# Proiect_TSC_v50.net
KiCad netlist of a schematic drawn in EAGLE
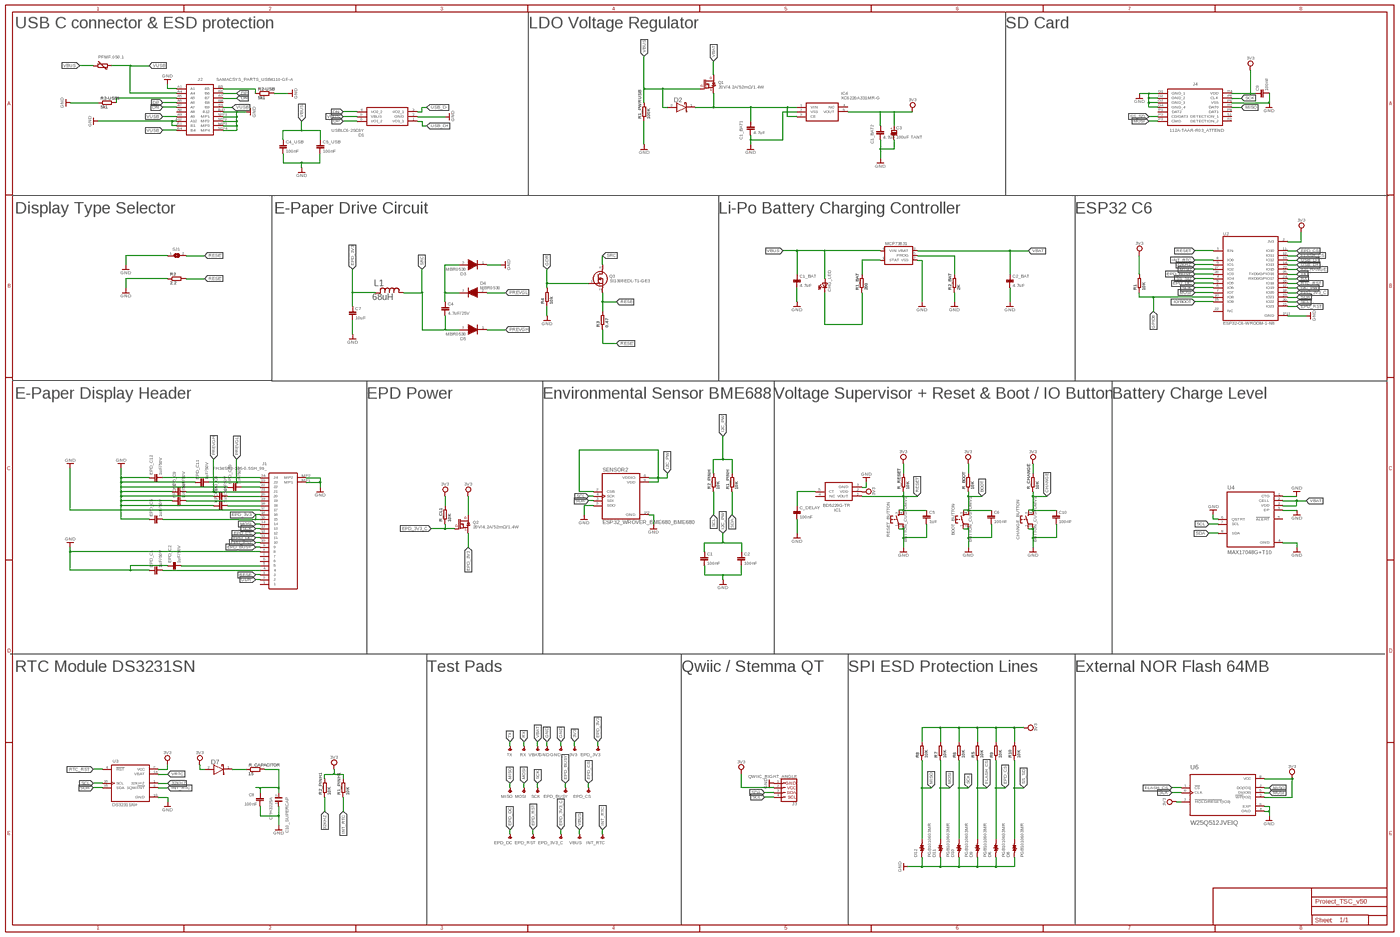
[diagram p0: schematic, sheet 1, overview]
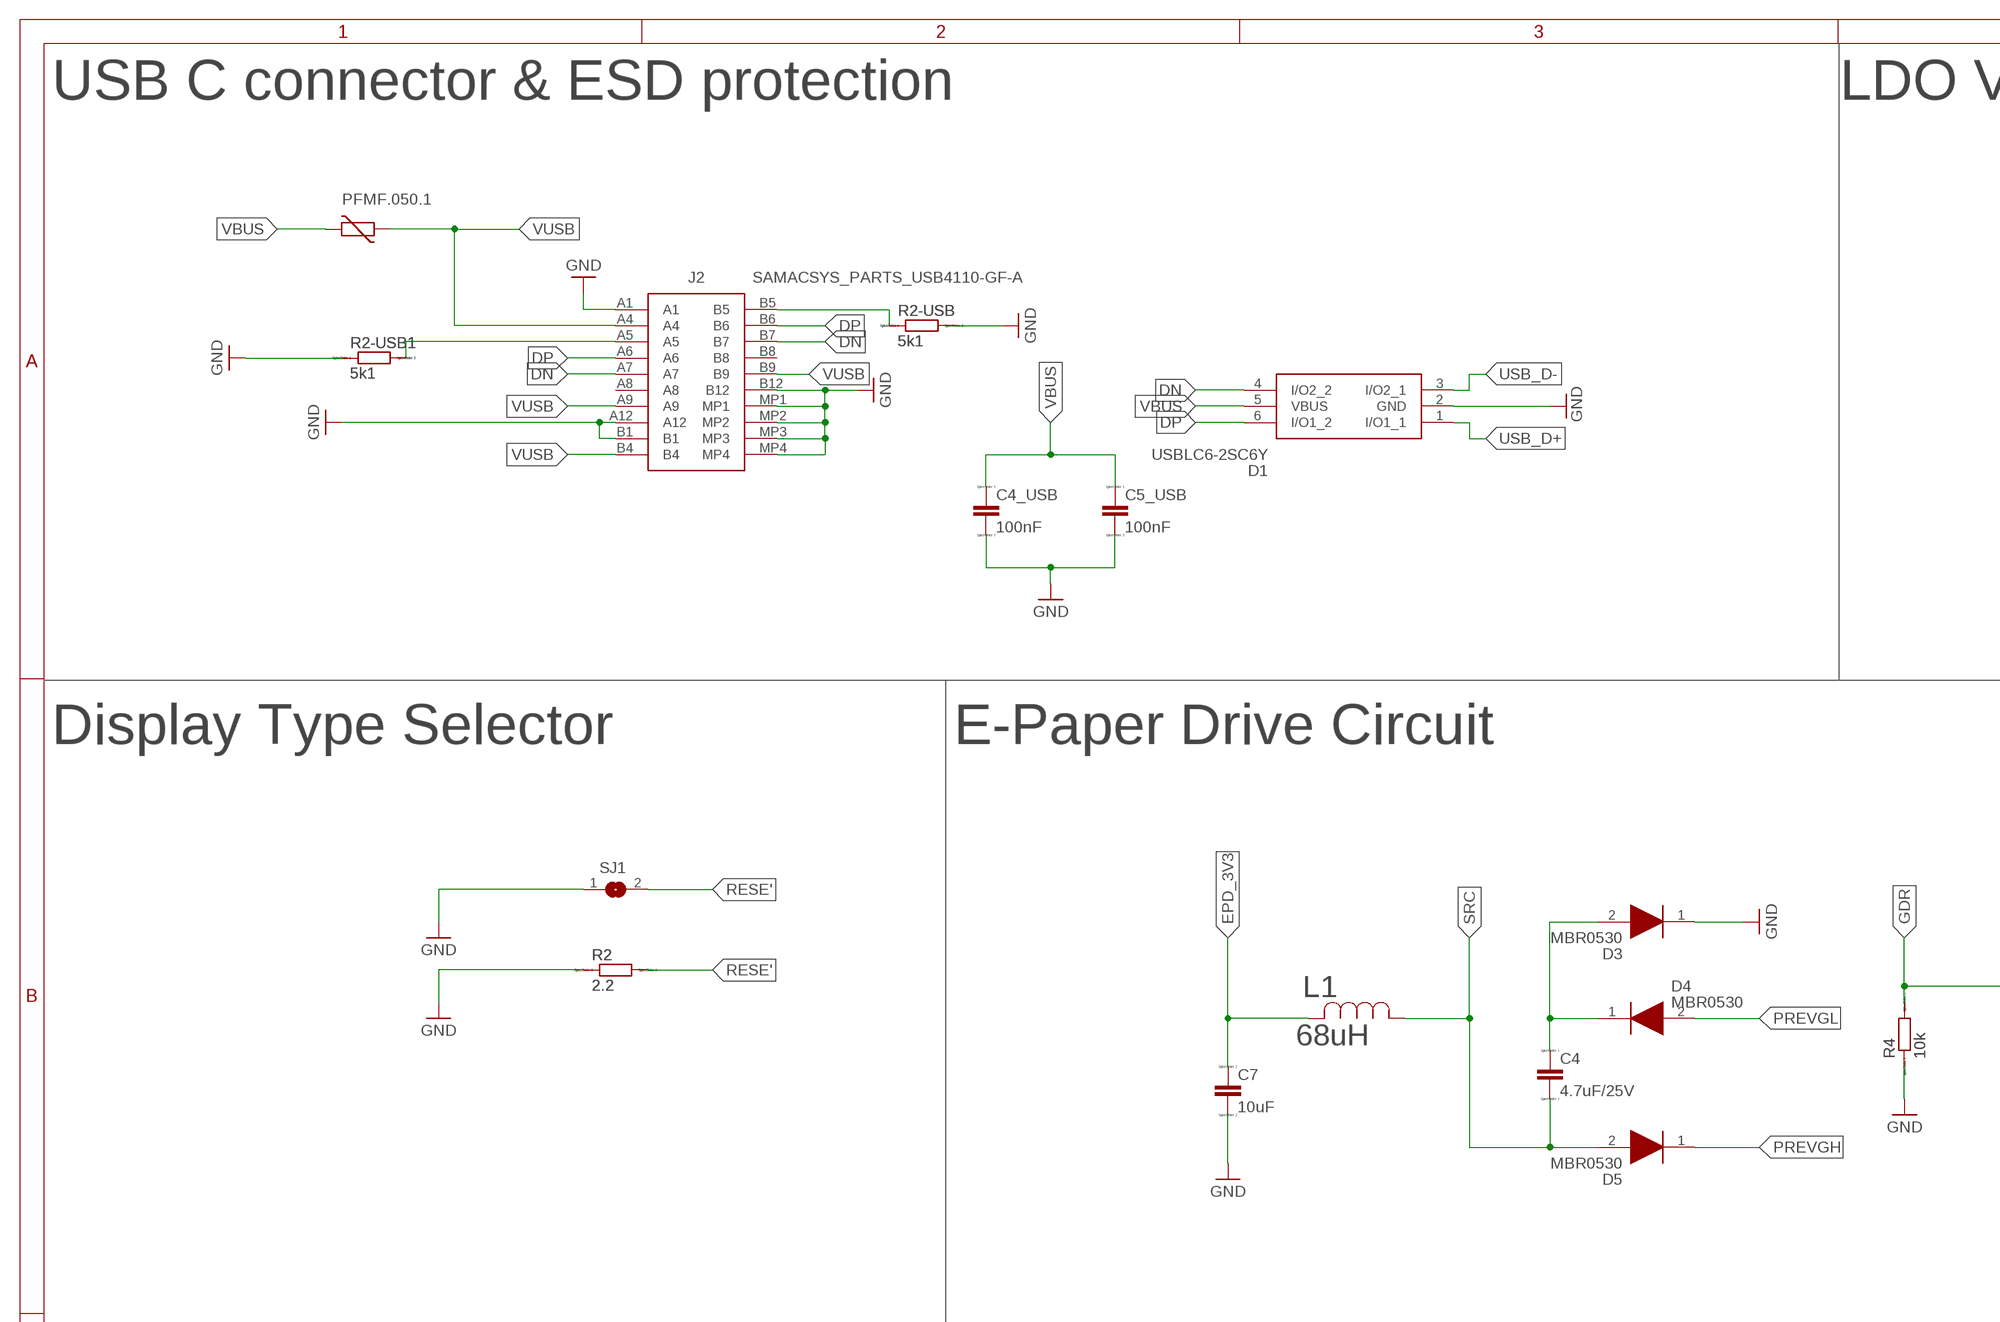
[diagram p1: schematic, sheet 1, part 1 of 4]
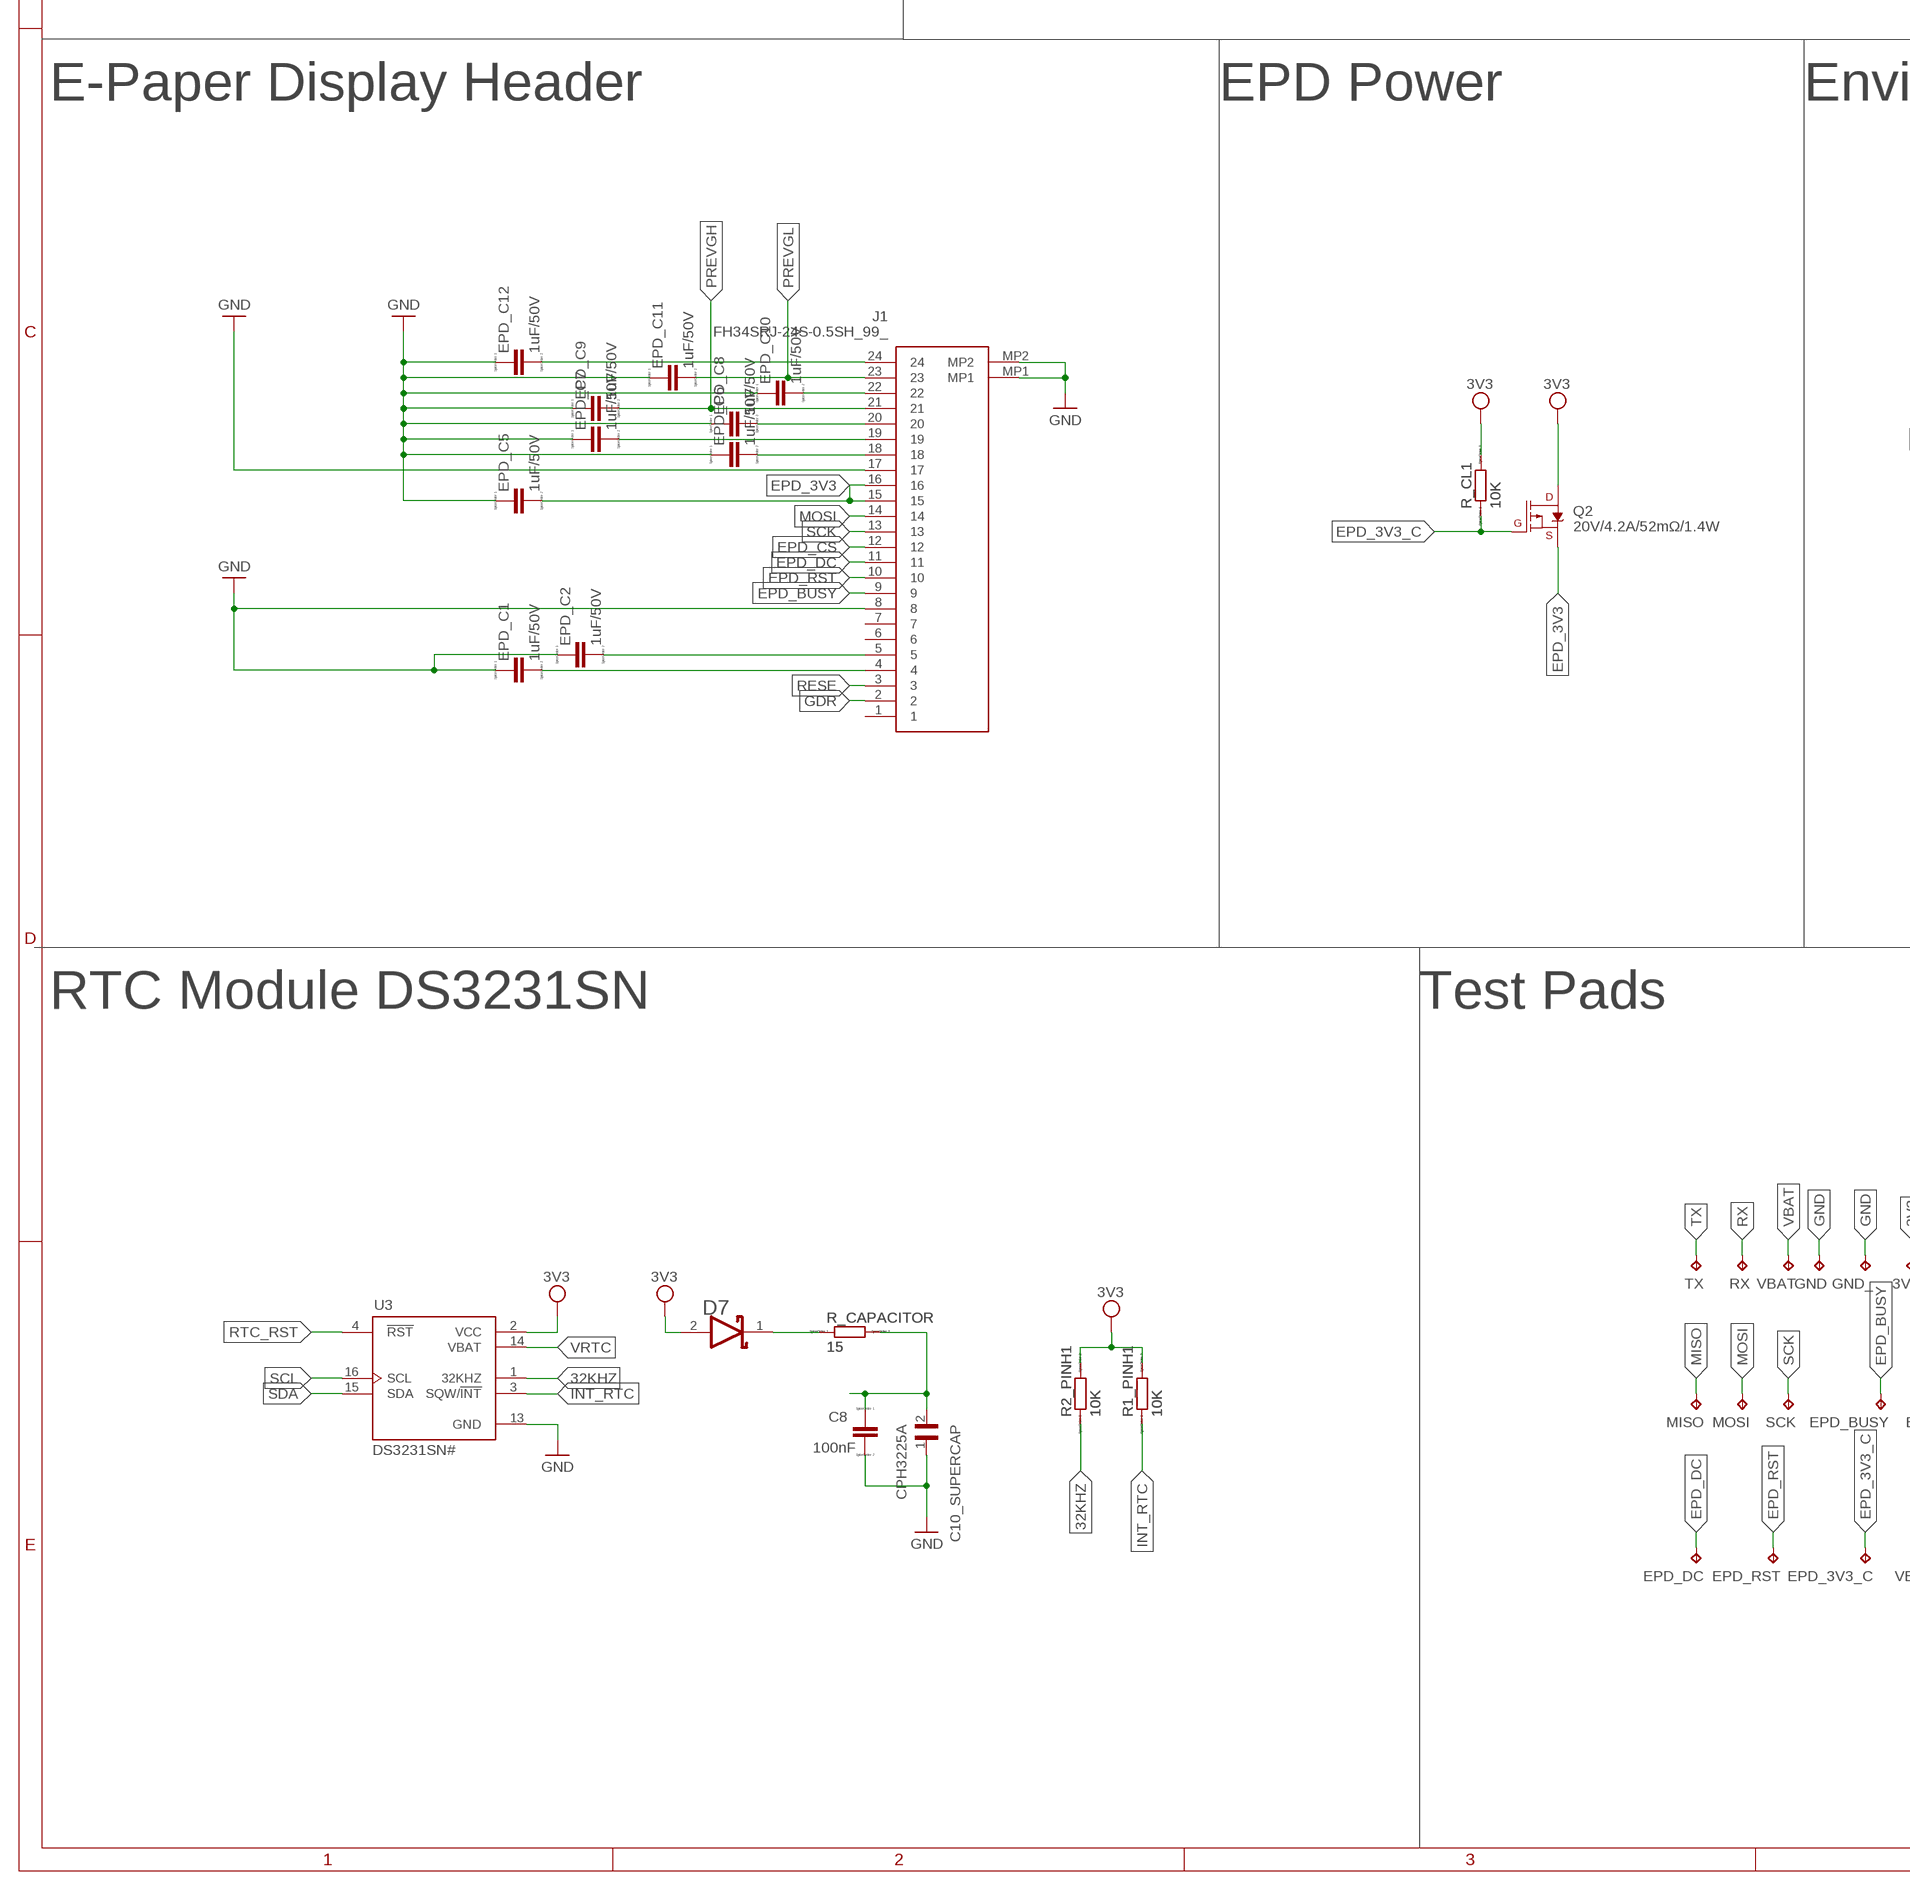
[diagram p2: schematic, sheet 1, part 2 of 4]
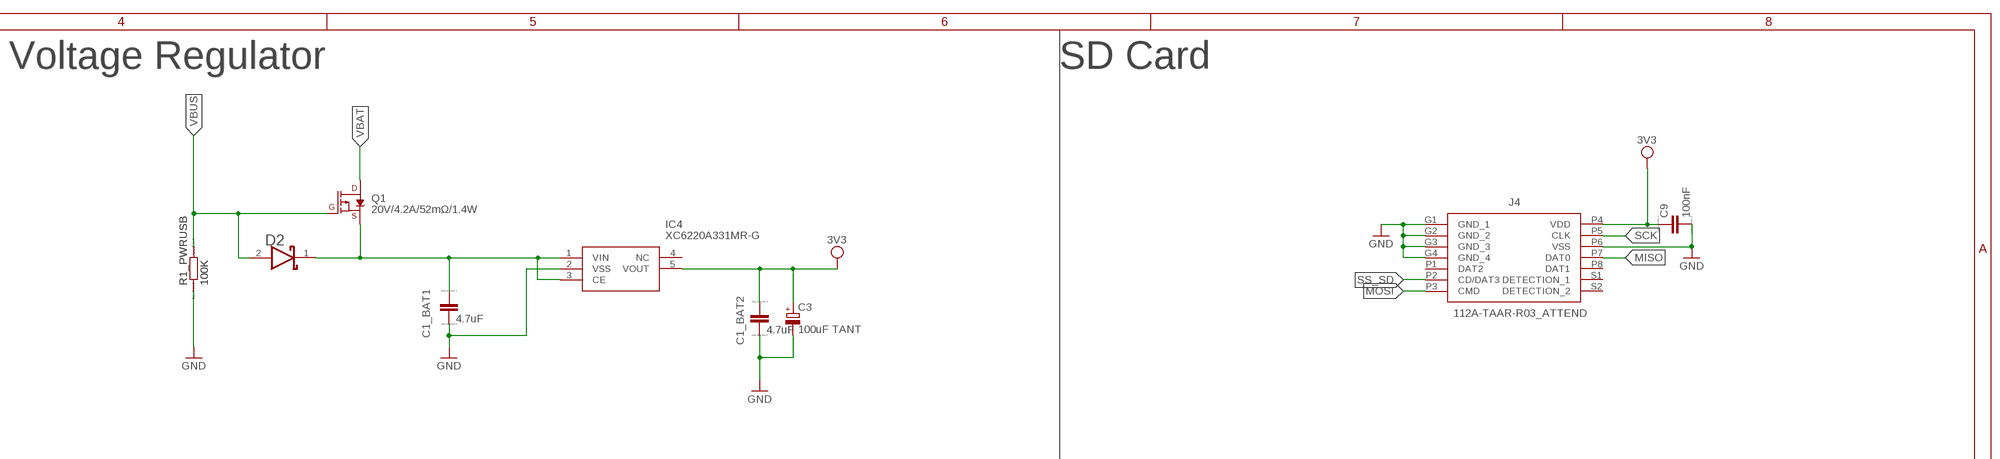
[diagram p3: schematic, sheet 1, part 3 of 4]
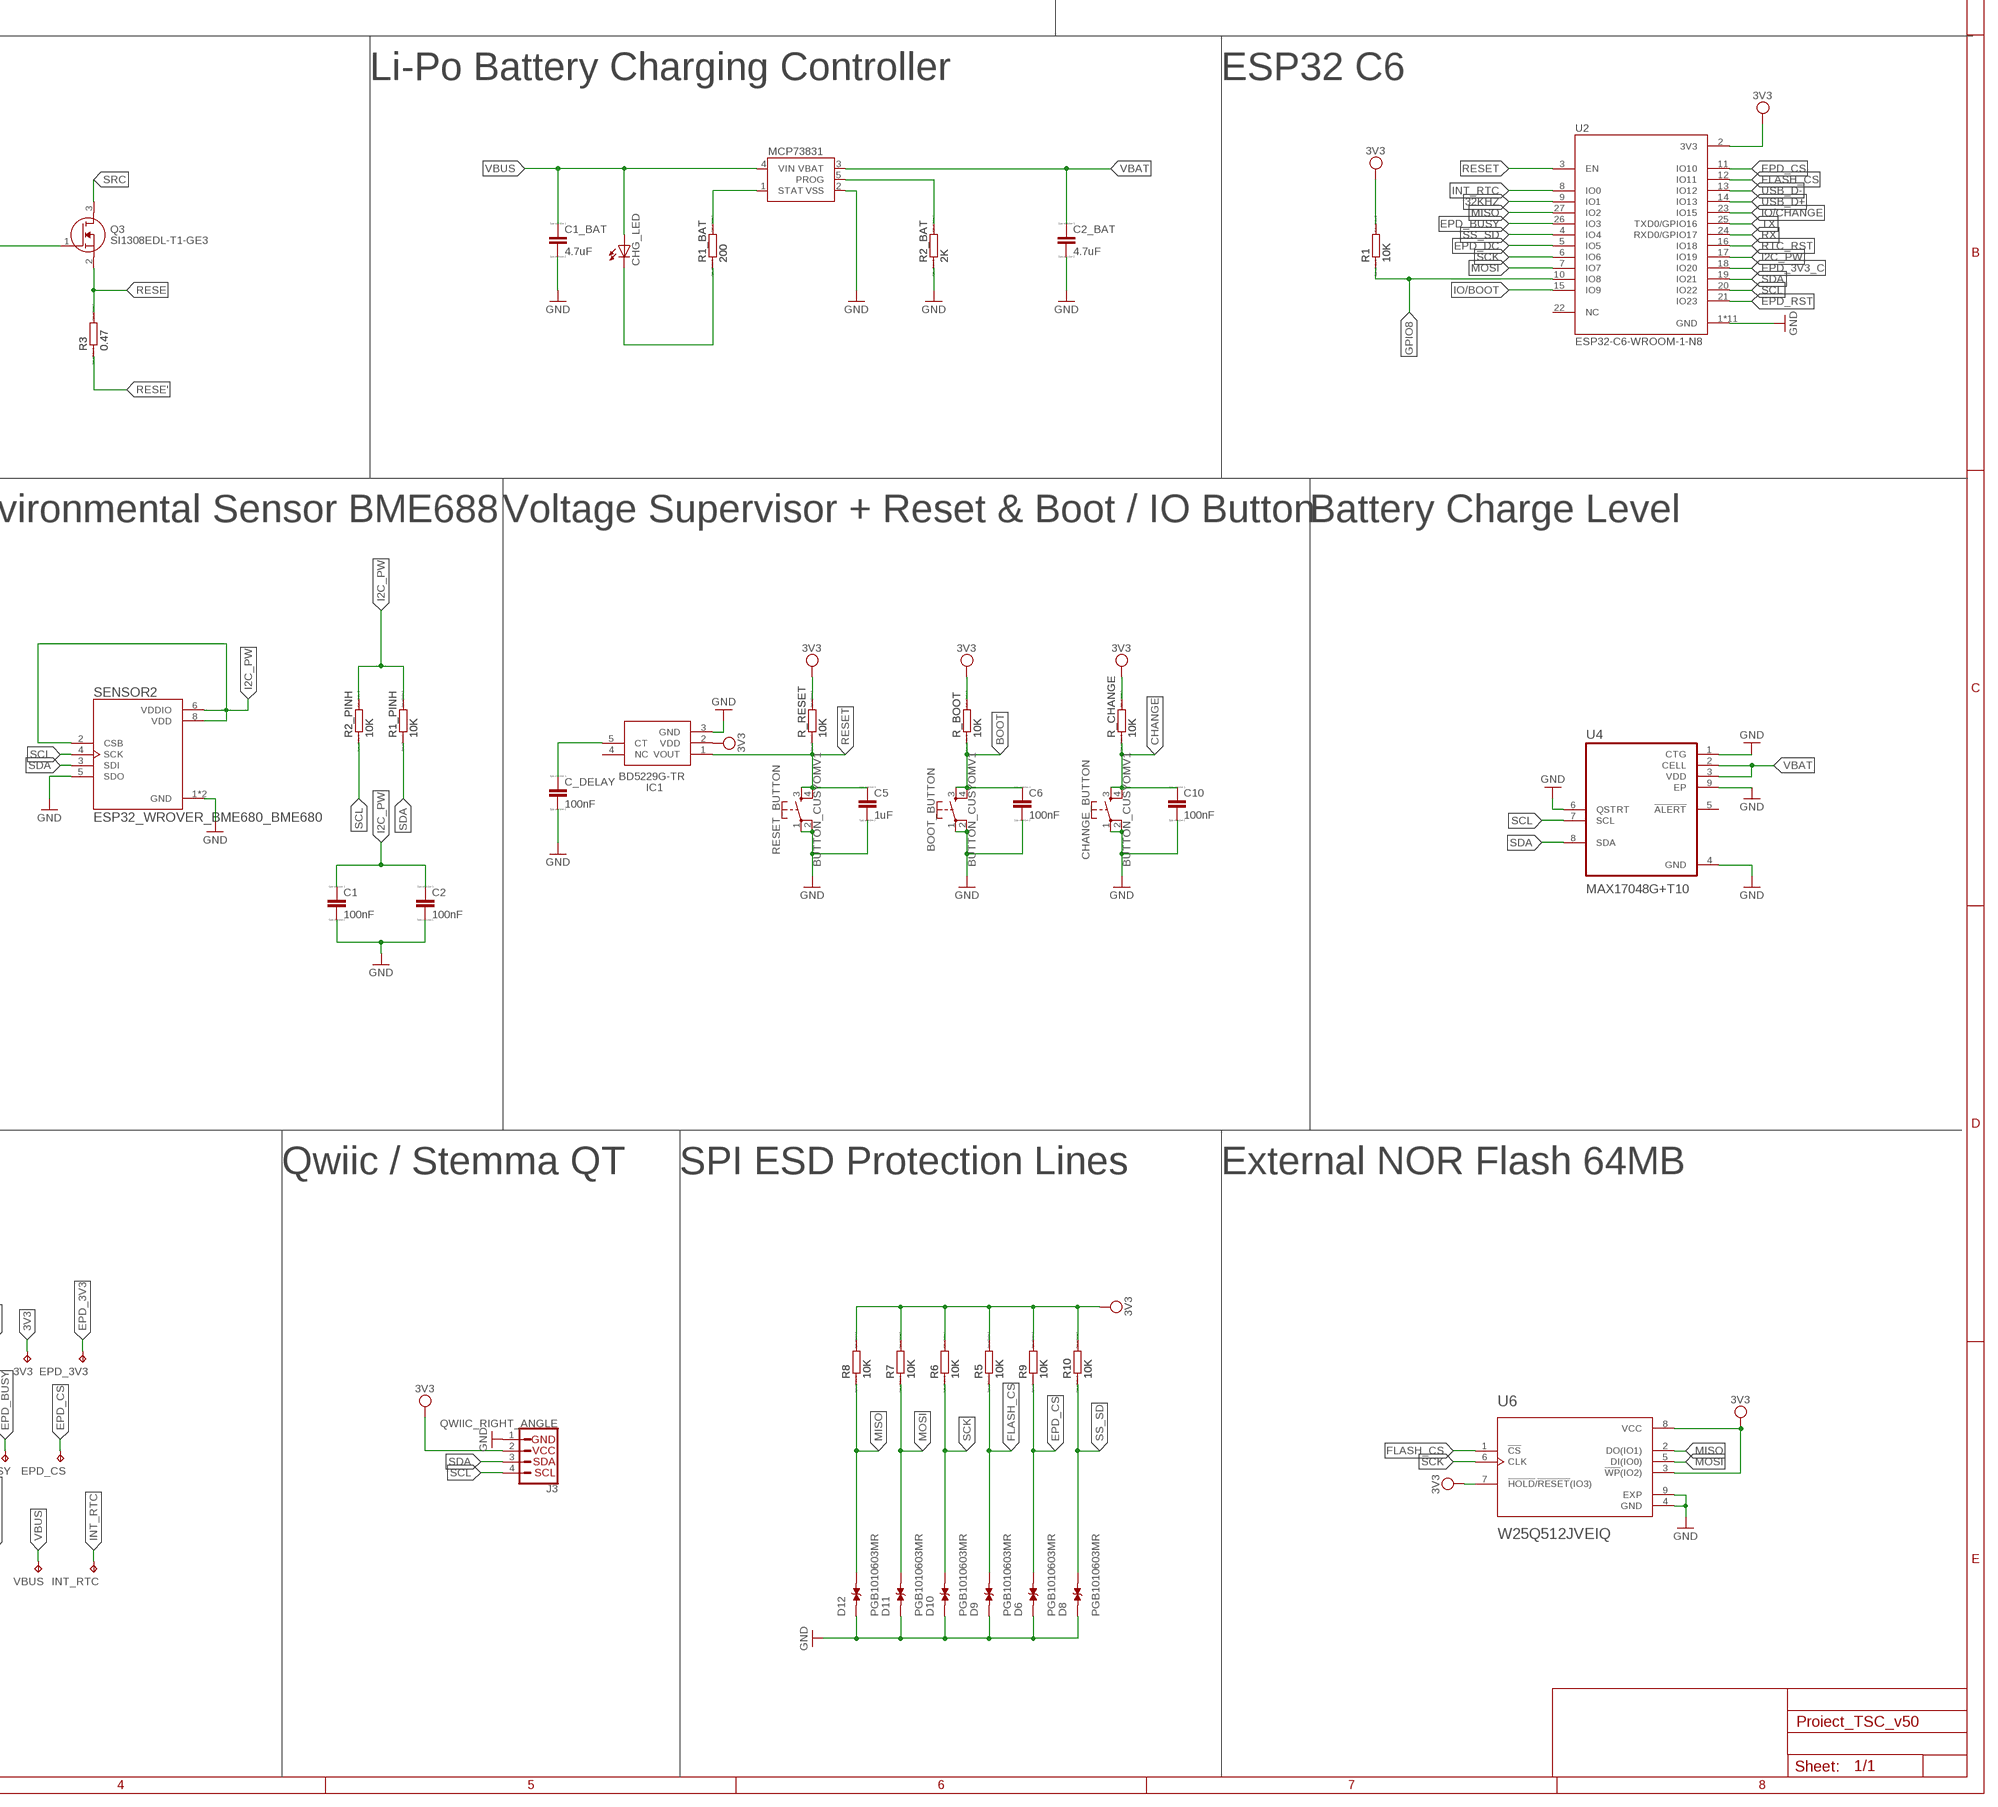
[diagram p4: schematic, sheet 1, part 4 of 4]

(export (version "E")
  (design (tool "Eeschema 10.0.6"))
  (components
    (comp (ref "3V3")
      (value "TPTP20R")
      (footprint "eagle-import:TP20R")
      (libsource (lib "eagle-import") (part "TPTP20R"))
    )
    (comp (ref "BOOT_BUTTON")
      (value "BUTTON_CUSYOMV1")
      (footprint "eagle-import:MYBUTTON")
      (libsource (lib "eagle-import") (part "BUTTON_CUSYOMV1"))
    )
    (comp (ref "C1")
      (value "100nF")
      (footprint "eagle-import:ESP32_WROVER_EAGLE-LTSPICE_C0402")
      (libsource (lib "eagle-import") (part "ESP32_WROVER_EAGLE-LTSPICE_CC0402"))
    )
    (comp (ref "C1_BAT")
      (value "4.7uF")
      (footprint "eagle-import:ESP32_WROVER_EAGLE-LTSPICE_C0402")
      (libsource (lib "eagle-import") (part "ESP32_WROVER_EAGLE-LTSPICE_CC0402"))
    )
    (comp (ref "C1_BAT1")
      (value "4.7uF")
      (footprint "eagle-import:ESP32_WROVER_EAGLE-LTSPICE_C0402")
      (libsource (lib "eagle-import") (part "ESP32_WROVER_EAGLE-LTSPICE_CC0402"))
    )
    (comp (ref "C1_BAT2")
      (value "4.7uF")
      (footprint "eagle-import:ESP32_WROVER_EAGLE-LTSPICE_C0402")
      (libsource (lib "eagle-import") (part "ESP32_WROVER_EAGLE-LTSPICE_CC0402"))
    )
    (comp (ref "C2")
      (value "100nF")
      (footprint "eagle-import:ESP32_WROVER_EAGLE-LTSPICE_C0402")
      (libsource (lib "eagle-import") (part "ESP32_WROVER_EAGLE-LTSPICE_CC0402"))
    )
    (comp (ref "C2_BAT")
      (value "4.7uF")
      (footprint "eagle-import:ESP32_WROVER_EAGLE-LTSPICE_C0402")
      (libsource (lib "eagle-import") (part "ESP32_WROVER_EAGLE-LTSPICE_CC0402"))
    )
    (comp (ref "C3")
      (value "100uF TANT")
      (footprint "eagle-import:RCL_CT3528")
      (libsource (lib "eagle-import") (part "RCL_CPOL-EUCT3528"))
    )
    (comp (ref "C4")
      (value "4.7uF/25V")
      (footprint "eagle-import:ESP32_WROVER_EAGLE-LTSPICE_C0402")
      (libsource (lib "eagle-import") (part "ESP32_WROVER_EAGLE-LTSPICE_CC0402"))
    )
    (comp (ref "C4_USB")
      (value "100nF")
      (footprint "eagle-import:ESP32_WROVER_EAGLE-LTSPICE_C0402")
      (libsource (lib "eagle-import") (part "ESP32_WROVER_EAGLE-LTSPICE_CC0402"))
    )
    (comp (ref "C5")
      (value "1uF")
      (footprint "eagle-import:EAGLE-LTSPICE_C0402")
      (libsource (lib "eagle-import") (part "EAGLE-LTSPICE_CC0402"))
    )
    (comp (ref "C5_USB")
      (value "100nF")
      (footprint "eagle-import:ESP32_WROVER_EAGLE-LTSPICE_C0402")
      (libsource (lib "eagle-import") (part "ESP32_WROVER_EAGLE-LTSPICE_CC0402"))
    )
    (comp (ref "C6")
      (value "100nF")
      (footprint "eagle-import:EAGLE-LTSPICE_C0402")
      (libsource (lib "eagle-import") (part "EAGLE-LTSPICE_CC0402"))
    )
    (comp (ref "C7")
      (value "10uF")
      (footprint "eagle-import:EAGLE-LTSPICE_C0402")
      (libsource (lib "eagle-import") (part "EAGLE-LTSPICE_CC0402"))
    )
    (comp (ref "C8")
      (value "100nF")
      (footprint "eagle-import:EAGLE-LTSPICE_C0402")
      (libsource (lib "eagle-import") (part "EAGLE-LTSPICE_CC0402"))
    )
    (comp (ref "C9")
      (value "100nF")
      (footprint "eagle-import:ESP32_WROVER_EAGLE-LTSPICE_C0402")
      (libsource (lib "eagle-import") (part "ESP32_WROVER_EAGLE-LTSPICE_CC0402"))
    )
    (comp (ref "C10")
      (value "100nF")
      (footprint "eagle-import:EAGLE-LTSPICE_C0402")
      (libsource (lib "eagle-import") (part "EAGLE-LTSPICE_CC0402"))
    )
    (comp (ref "C10_SUPERCAP")
      (value "CPH3225A")
      (footprint "eagle-import:CAPCP3225X100N")
      (fields (field (name "MF") "Seiko Instruments"))
      (libsource (lib "eagle-import") (part "CPH3225A"))
    )
    (comp (ref "CHANGE_BUTTON")
      (value "BUTTON_CUSYOMV1")
      (footprint "eagle-import:MYBUTTON")
      (libsource (lib "eagle-import") (part "BUTTON_CUSYOMV1"))
    )
    (comp (ref "CHG_LED")
      (value "ADAFRUIT_LEDCHIP-LED0603")
      (footprint "eagle-import:ADAFRUIT_CHIP-LED0603")
      (libsource (lib "eagle-import") (part "ADAFRUIT_LEDCHIP-LED0603"))
    )
    (comp (ref "C_DELAY")
      (value "100nF")
      (footprint "eagle-import:EAGLE-LTSPICE_C0402")
      (libsource (lib "eagle-import") (part "EAGLE-LTSPICE_CC0402"))
    )
    (comp (ref "D1")
      (value "USBLC6-2SC6Y")
      (footprint "eagle-import:SOT95P280X145-6N")
      (fields (field (name "MF") "STMicroelectronics"))
      (libsource (lib "eagle-import") (part "USBLC6-2SC6Y"))
    )
    (comp (ref "D2")
      (value "ESP32_WROVER_AVX---SD0805S020S1R0_AVX_SD0805S020S1R0_0_0AVX_SD0805S020S1R0_0_0")
      (footprint "eagle-import:ESP32_WROVER_AVX---SD0805S020S1R0_AVX_SD0805S020S1R0_0")
      (fields
        (field (name "DIGIKEY_PART_NUMBER") "478-7800-1-ND")
        (field (name "MF") "AVX")
        (field (name "MOUSER_PART_NUMBER") "581-SD0805S020S1R0")
      )
      (libsource (lib "eagle-import") (part "ESP32_WROVER_AVX---SD0805S020S1R0_AVX_SD0805S020S1R0_0_0AVX_SD0805S020S1R0_0_0"))
    )
    (comp (ref "D3")
      (value "MBR0530")
      (footprint "eagle-import:SOD3716X135N")
      (fields (field (name "MF") "ON Semiconductor"))
      (libsource (lib "eagle-import") (part "MBR0530"))
    )
    (comp (ref "D4")
      (value "MBR0530")
      (footprint "eagle-import:SOD3716X135N")
      (fields (field (name "MF") "ON Semiconductor"))
      (libsource (lib "eagle-import") (part "MBR0530"))
    )
    (comp (ref "D5")
      (value "MBR0530")
      (footprint "eagle-import:SOD3716X135N")
      (fields (field (name "MF") "ON Semiconductor"))
      (libsource (lib "eagle-import") (part "MBR0530"))
    )
    (comp (ref "D6")
      (value "PGB1010603MR")
      (footprint "eagle-import:DIOC1608X36N")
      (fields (field (name "MF") "Littelfuse Inc."))
      (libsource (lib "eagle-import") (part "PGB1010603MR"))
    )
    (comp (ref "D7")
      (value "ESP32_WROVER_AVX---SD0805S020S1R0_AVX_SD0805S020S1R0_0_0AVX_SD0805S020S1R0_0_0")
      (footprint "eagle-import:ESP32_WROVER_AVX---SD0805S020S1R0_AVX_SD0805S020S1R0_0")
      (fields
        (field (name "DIGIKEY_PART_NUMBER") "478-7800-1-ND")
        (field (name "MF") "AVX")
        (field (name "MOUSER_PART_NUMBER") "581-SD0805S020S1R0")
      )
      (libsource (lib "eagle-import") (part "ESP32_WROVER_AVX---SD0805S020S1R0_AVX_SD0805S020S1R0_0_0AVX_SD0805S020S1R0_0_0"))
    )
    (comp (ref "D8")
      (value "PGB1010603MR")
      (footprint "eagle-import:DIOC1608X36N")
      (fields (field (name "MF") "Littelfuse Inc."))
      (libsource (lib "eagle-import") (part "PGB1010603MR"))
    )
    (comp (ref "D9")
      (value "PGB1010603MR")
      (footprint "eagle-import:DIOC1608X36N")
      (fields (field (name "MF") "Littelfuse Inc."))
      (libsource (lib "eagle-import") (part "PGB1010603MR"))
    )
    (comp (ref "D10")
      (value "PGB1010603MR")
      (footprint "eagle-import:DIOC1608X36N")
      (fields (field (name "MF") "Littelfuse Inc."))
      (libsource (lib "eagle-import") (part "PGB1010603MR"))
    )
    (comp (ref "D11")
      (value "PGB1010603MR")
      (footprint "eagle-import:DIOC1608X36N")
      (fields (field (name "MF") "Littelfuse Inc."))
      (libsource (lib "eagle-import") (part "PGB1010603MR"))
    )
    (comp (ref "D12")
      (value "PGB1010603MR")
      (footprint "eagle-import:DIOC1608X36N")
      (fields (field (name "MF") "Littelfuse Inc."))
      (libsource (lib "eagle-import") (part "PGB1010603MR"))
    )
    (comp (ref "EPD_3V3")
      (value "TPTP20R")
      (footprint "eagle-import:TP20R")
      (libsource (lib "eagle-import") (part "TPTP20R"))
    )
    (comp (ref "EPD_3V3_C")
      (value "TPTP20R")
      (footprint "eagle-import:TP20R")
      (libsource (lib "eagle-import") (part "TPTP20R"))
    )
    (comp (ref "EPD_BUSY")
      (value "TPTP20R")
      (footprint "eagle-import:TP20R")
      (libsource (lib "eagle-import") (part "TPTP20R"))
    )
    (comp (ref "EPD_C1")
      (value "1uF/50V")
      (footprint "eagle-import:ESP32_WROVER_EAGLE-LTSPICE_C0402")
      (libsource (lib "eagle-import") (part "ESP32_WROVER_EAGLE-LTSPICE_CC0402"))
    )
    (comp (ref "EPD_C2")
      (value "1uF/50V")
      (footprint "eagle-import:ESP32_WROVER_EAGLE-LTSPICE_C0402")
      (libsource (lib "eagle-import") (part "ESP32_WROVER_EAGLE-LTSPICE_CC0402"))
    )
    (comp (ref "EPD_C5")
      (value "1uF/50V")
      (footprint "eagle-import:ESP32_WROVER_EAGLE-LTSPICE_C0402")
      (libsource (lib "eagle-import") (part "ESP32_WROVER_EAGLE-LTSPICE_CC0402"))
    )
    (comp (ref "EPD_C6")
      (value "1uF/50V")
      (footprint "eagle-import:ESP32_WROVER_EAGLE-LTSPICE_C0402")
      (libsource (lib "eagle-import") (part "ESP32_WROVER_EAGLE-LTSPICE_CC0402"))
    )
    (comp (ref "EPD_C7")
      (value "1uF/50V")
      (footprint "eagle-import:ESP32_WROVER_EAGLE-LTSPICE_C0402")
      (libsource (lib "eagle-import") (part "ESP32_WROVER_EAGLE-LTSPICE_CC0402"))
    )
    (comp (ref "EPD_C8")
      (value "1uF/50V")
      (footprint "eagle-import:ESP32_WROVER_EAGLE-LTSPICE_C0402")
      (libsource (lib "eagle-import") (part "ESP32_WROVER_EAGLE-LTSPICE_CC0402"))
    )
    (comp (ref "EPD_C9")
      (value "1uF/50V")
      (footprint "eagle-import:ESP32_WROVER_EAGLE-LTSPICE_C0402")
      (libsource (lib "eagle-import") (part "ESP32_WROVER_EAGLE-LTSPICE_CC0402"))
    )
    (comp (ref "EPD_C10")
      (value "1uF/50V")
      (footprint "eagle-import:ESP32_WROVER_EAGLE-LTSPICE_C0402")
      (libsource (lib "eagle-import") (part "ESP32_WROVER_EAGLE-LTSPICE_CC0402"))
    )
    (comp (ref "EPD_C11")
      (value "1uF/50V")
      (footprint "eagle-import:ESP32_WROVER_EAGLE-LTSPICE_C0402")
      (libsource (lib "eagle-import") (part "ESP32_WROVER_EAGLE-LTSPICE_CC0402"))
    )
    (comp (ref "EPD_C12")
      (value "1uF/50V")
      (footprint "eagle-import:ESP32_WROVER_EAGLE-LTSPICE_C0402")
      (libsource (lib "eagle-import") (part "ESP32_WROVER_EAGLE-LTSPICE_CC0402"))
    )
    (comp (ref "EPD_CS")
      (value "TPTP20R")
      (footprint "eagle-import:TP20R")
      (libsource (lib "eagle-import") (part "TPTP20R"))
    )
    (comp (ref "EPD_DC")
      (value "TPTP20R")
      (footprint "eagle-import:TP20R")
      (libsource (lib "eagle-import") (part "TPTP20R"))
    )
    (comp (ref "EPD_RST")
      (value "TPTP20R")
      (footprint "eagle-import:TP20R")
      (libsource (lib "eagle-import") (part "TPTP20R"))
    )
    (comp (ref "GND")
      (value "TPTP20R")
      (footprint "eagle-import:TP20R")
      (libsource (lib "eagle-import") (part "TPTP20R"))
    )
    (comp (ref "GND_")
      (value "TPTP20R")
      (footprint "eagle-import:TP20R")
      (libsource (lib "eagle-import") (part "TPTP20R"))
    )
    (comp (ref "IC1")
      (value "BD5229G-TR")
      (footprint "eagle-import:SOT95P280X125-5N")
      (fields (field (name "MOUSER_PART_NUMBER") "755-BD5229G-TR"))
      (libsource (lib "eagle-import") (part "BD5229G-TR"))
    )
    (comp (ref "IC4")
      (value "XC6220A331MR-G")
      (footprint "eagle-import:SOT95P280X120-5N")
      (fields (field (name "MOUSER_PART_NUMBER") "865-XC6220A331MR-G"))
      (libsource (lib "eagle-import") (part "XC6220A331MR-G"))
    )
    (comp (ref "INT_RTC")
      (value "TPTP20R")
      (footprint "eagle-import:TP20R")
      (libsource (lib "eagle-import") (part "TPTP20R"))
    )
    (comp (ref "J1")
      (value "FH34SRJ-24S-0.5SH_99_")
      (footprint "eagle-import:FH34SRJ24S05SH99")
      (fields
        (field (name "MANUFACTURER_PART_NUMBER") "FH34SRJ-24S-0.5SH(99)")
        (field (name "MOUSER_PART_NUMBER") "798-FH34SRJ24S05SH99")
      )
      (libsource (lib "eagle-import") (part "FH34SRJ-24S-0.5SH_99_"))
    )
    (comp (ref "J2")
      (value "SAMACSYS_PARTS_USB4110-GF-A")
      (footprint "eagle-import:SAMACSYS_PARTS_USB4110GFA")
      (fields
        (field (name "MANUFACTURER_PART_NUMBER") "USB4110-GF-A")
        (field (name "MOUSER_PART_NUMBER") "640-USB4110-GF-A")
      )
      (libsource (lib "eagle-import") (part "SAMACSYS_PARTS_USB4110-GF-A"))
    )
    (comp (ref "J3")
      (value "QWIIC_RIGHT_ANGLE")
      (footprint "eagle-import:JST04_1MM_RA")
      (libsource (lib "eagle-import") (part "QWIIC_CONNECTORJS-1MM"))
    )
    (comp (ref "J4")
      (value "112A-TAAR-R03_ATTEND")
      (footprint "eagle-import:112ATAARR03ATTEND")
      (fields (field (name "MANUFACTURER_PART_NUMBER") "112A-TAAR-R03 ATTEND"))
      (libsource (lib "eagle-import") (part "112A-TAAR-R03_ATTEND"))
    )
    (comp (ref "L1")
      (value "68uH")
      (footprint "eagle-import:IND_4828-WE-TPC_WRE")
      (fields
        (field (name "MANUFACTURER_PART_NUMBER") "744043680")
        (field (name "COPYRIGHT") "Copyright (C) 2024 Ultra Librarian. All rights reserved.")
      )
      (libsource (lib "eagle-import") (part "744043680IND_4828-WE-TPC_WRE"))
    )
    (comp (ref "MCP73831")
      (value "ESP32_WROVER_SPARKFUN-IC-POWER_MCP73831")
      (footprint "eagle-import:ESP32_WROVER_SPARKFUN-IC-POWER_SOT23-5")
      (libsource (lib "eagle-import") (part "ESP32_WROVER_SPARKFUN-IC-POWER_MCP73831"))
    )
    (comp (ref "MISO")
      (value "TPTP20R")
      (footprint "eagle-import:TP20R")
      (libsource (lib "eagle-import") (part "TPTP20R"))
    )
    (comp (ref "MOSI")
      (value "TPTP20R")
      (footprint "eagle-import:TP20R")
      (libsource (lib "eagle-import") (part "TPTP20R"))
    )
    (comp (ref "PFMF.050.1")
      (value "ESP32C6_VARISTORCN1812")
      (footprint "eagle-import:ESP32C6_VARISTOR_CT_CN1812")
      (libsource (lib "eagle-import") (part "ESP32C6_VARISTORCN1812"))
    )
    (comp (ref "Q1")
      (value "20V/4.2A/52mΩ/1.4W")
      (footprint "eagle-import:ESP32_WROVER_SPARKFUN-DISCRETESEMI_SOT23-3")
      (libsource (lib "eagle-import") (part "ESP32_WROVER_SPARKFUN-DISCRETESEMI_MOSFET_PCH-DMG2305UX-7"))
    )
    (comp (ref "Q2")
      (value "20V/4.2A/52mΩ/1.4W")
      (footprint "eagle-import:ESP32_WROVER_SPARKFUN-DISCRETESEMI_SOT23-3")
      (libsource (lib "eagle-import") (part "ESP32_WROVER_SPARKFUN-DISCRETESEMI_MOSFET_PCH-DMG2305UX-7"))
    )
    (comp (ref "Q3")
      (value "SI1308EDL-T1-GE3")
      (footprint "eagle-import:SOT65P210X110-3N")
      (fields (field (name "MF") "Vishay Siliconix"))
      (libsource (lib "eagle-import") (part "SI1308EDL-T1-GE3"))
    )
    (comp (ref "R1")
      (value "10K")
      (footprint "eagle-import:ESP32_WROVER_EAGLE-LTSPICE_R0402")
      (libsource (lib "eagle-import") (part "ESP32_WROVER_EAGLE-LTSPICE_RR0402"))
    )
    (comp (ref "R1_BAT")
      (value "200")
      (footprint "eagle-import:ESP32_WROVER_EAGLE-LTSPICE_R0402")
      (libsource (lib "eagle-import") (part "ESP32_WROVER_EAGLE-LTSPICE_RR0402"))
    )
    (comp (ref "R1_PINH")
      (value "10K")
      (footprint "eagle-import:ESP32_WROVER_EAGLE-LTSPICE_R0402")
      (libsource (lib "eagle-import") (part "ESP32_WROVER_EAGLE-LTSPICE_RR0402"))
    )
    (comp (ref "R1_PINH1")
      (value "10K")
      (footprint "eagle-import:ESP32_WROVER_EAGLE-LTSPICE_R0402")
      (libsource (lib "eagle-import") (part "ESP32_WROVER_EAGLE-LTSPICE_RR0402"))
    )
    (comp (ref "R1_PWRUSB")
      (value "100K")
      (footprint "eagle-import:ESP32_WROVER_EAGLE-LTSPICE_R0402")
      (libsource (lib "eagle-import") (part "ESP32_WROVER_EAGLE-LTSPICE_RR0402"))
    )
    (comp (ref "R2")
      (value "2.2")
      (footprint "eagle-import:ESP32_WROVER_EAGLE-LTSPICE_R0402")
      (libsource (lib "eagle-import") (part "ESP32_WROVER_EAGLE-LTSPICE_RR0402"))
    )
    (comp (ref "R2-USB")
      (value "5k1")
      (footprint "eagle-import:ESP32_WROVER_EAGLE-LTSPICE_R0402")
      (libsource (lib "eagle-import") (part "ESP32_WROVER_EAGLE-LTSPICE_RR0402"))
    )
    (comp (ref "R2-USB1")
      (value "5k1")
      (footprint "eagle-import:ESP32_WROVER_EAGLE-LTSPICE_R0402")
      (libsource (lib "eagle-import") (part "ESP32_WROVER_EAGLE-LTSPICE_RR0402"))
    )
    (comp (ref "R2_BAT")
      (value "2K")
      (footprint "eagle-import:ESP32_WROVER_EAGLE-LTSPICE_R0402")
      (libsource (lib "eagle-import") (part "ESP32_WROVER_EAGLE-LTSPICE_RR0402"))
    )
    (comp (ref "R2_PINH")
      (value "10K")
      (footprint "eagle-import:ESP32_WROVER_EAGLE-LTSPICE_R0402")
      (libsource (lib "eagle-import") (part "ESP32_WROVER_EAGLE-LTSPICE_RR0402"))
    )
    (comp (ref "R2_PINH1")
      (value "10K")
      (footprint "eagle-import:ESP32_WROVER_EAGLE-LTSPICE_R0402")
      (libsource (lib "eagle-import") (part "ESP32_WROVER_EAGLE-LTSPICE_RR0402"))
    )
    (comp (ref "R3")
      (value "0.47")
      (footprint "eagle-import:ESP32_WROVER_EAGLE-LTSPICE_R0402")
      (libsource (lib "eagle-import") (part "ESP32_WROVER_EAGLE-LTSPICE_RR0402"))
    )
    (comp (ref "R4")
      (value "10k")
      (footprint "eagle-import:ESP32_WROVER_EAGLE-LTSPICE_R0402")
      (libsource (lib "eagle-import") (part "ESP32_WROVER_EAGLE-LTSPICE_RR0402"))
    )
    (comp (ref "R5")
      (value "10K")
      (footprint "eagle-import:ESP32_WROVER_EAGLE-LTSPICE_R0402")
      (libsource (lib "eagle-import") (part "ESP32_WROVER_EAGLE-LTSPICE_RR0402"))
    )
    (comp (ref "R6")
      (value "10K")
      (footprint "eagle-import:ESP32_WROVER_EAGLE-LTSPICE_R0402")
      (libsource (lib "eagle-import") (part "ESP32_WROVER_EAGLE-LTSPICE_RR0402"))
    )
    (comp (ref "R7")
      (value "10K")
      (footprint "eagle-import:ESP32_WROVER_EAGLE-LTSPICE_R0402")
      (libsource (lib "eagle-import") (part "ESP32_WROVER_EAGLE-LTSPICE_RR0402"))
    )
    (comp (ref "R8")
      (value "10K")
      (footprint "eagle-import:ESP32_WROVER_EAGLE-LTSPICE_R0402")
      (libsource (lib "eagle-import") (part "ESP32_WROVER_EAGLE-LTSPICE_RR0402"))
    )
    (comp (ref "R9")
      (value "10K")
      (footprint "eagle-import:ESP32_WROVER_EAGLE-LTSPICE_R0402")
      (libsource (lib "eagle-import") (part "ESP32_WROVER_EAGLE-LTSPICE_RR0402"))
    )
    (comp (ref "R10")
      (value "10K")
      (footprint "eagle-import:ESP32_WROVER_EAGLE-LTSPICE_R0402")
      (libsource (lib "eagle-import") (part "ESP32_WROVER_EAGLE-LTSPICE_RR0402"))
    )
    (comp (ref "RESET_BUTTON")
      (value "BUTTON_CUSYOMV1")
      (footprint "eagle-import:MYBUTTON")
      (libsource (lib "eagle-import") (part "BUTTON_CUSYOMV1"))
    )
    (comp (ref "RX")
      (value "TPTP20R")
      (footprint "eagle-import:TP20R")
      (libsource (lib "eagle-import") (part "TPTP20R"))
    )
    (comp (ref "R_BOOT")
      (value "10K")
      (footprint "eagle-import:ESP32_WROVER_EAGLE-LTSPICE_R0402")
      (libsource (lib "eagle-import") (part "ESP32_WROVER_EAGLE-LTSPICE_RR0402"))
    )
    (comp (ref "R_CAPACITOR")
      (value "15")
      (footprint "eagle-import:ESP32_WROVER_EAGLE-LTSPICE_R0402")
      (libsource (lib "eagle-import") (part "ESP32_WROVER_EAGLE-LTSPICE_RR0402"))
    )
    (comp (ref "R_CHANGE")
      (value "10K")
      (footprint "eagle-import:ESP32_WROVER_EAGLE-LTSPICE_R0402")
      (libsource (lib "eagle-import") (part "ESP32_WROVER_EAGLE-LTSPICE_RR0402"))
    )
    (comp (ref "R_CL1")
      (value "10K")
      (footprint "eagle-import:ESP32_WROVER_EAGLE-LTSPICE_R0402")
      (libsource (lib "eagle-import") (part "ESP32_WROVER_EAGLE-LTSPICE_RR0402"))
    )
    (comp (ref "R_RESET")
      (value "10K")
      (footprint "eagle-import:ESP32_WROVER_EAGLE-LTSPICE_R0402")
      (libsource (lib "eagle-import") (part "ESP32_WROVER_EAGLE-LTSPICE_RR0402"))
    )
    (comp (ref "SCK")
      (value "TPTP20R")
      (footprint "eagle-import:TP20R")
      (libsource (lib "eagle-import") (part "TPTP20R"))
    )
    (comp (ref "SENSOR2")
      (value "ESP32_WROVER_BME680_BME680")
      (footprint "eagle-import:ESP32_WROVER_BME680_PSON80P300X300X100-8N")
      (fields (field (name "MF") "Bosch Sensortec") (field (name "MP") "BME680"))
      (libsource (lib "eagle-import") (part "ESP32_WROVER_BME680_BME680"))
    )
    (comp (ref "SJ1") (value "SJ") (footprint "eagle-import:SJ") (libsource (lib "eagle-import") (part "SJ")))
    (comp (ref "TX")
      (value "TPTP20R")
      (footprint "eagle-import:TP20R")
      (libsource (lib "eagle-import") (part "TPTP20R"))
    )
    (comp (ref "U2")
      (value "ESP32-C6-WROOM-1-N8")
      (footprint "eagle-import:XCVR_ESP32-C6-WROOM-1-N8")
      (fields (field (name "MF") "Espressif Systems"))
      (libsource (lib "eagle-import") (part "ESP32-C6-WROOM-1-N8"))
    )
    (comp (ref "U3")
      (value "DS3231SN#")
      (footprint "eagle-import:SOIC127P1032X265-16N")
      (fields (field (name "MF") "Analog Devices"))
      (libsource (lib "eagle-import") (part "DS3231SN#"))
    )
    (comp (ref "U4")
      (value "MAX17048G+T10")
      (footprint "eagle-import:SON50P200X200X80-9N")
      (fields (field (name "MF") "Analog Devices"))
      (libsource (lib "eagle-import") (part "MAX17048G+T10"))
    )
    (comp (ref "U6")
      (value "W25Q512JVEIQ")
      (footprint "eagle-import:SON127P600X800X80-9N")
      (fields (field (name "MF") "Winbond Electronics"))
      (libsource (lib "eagle-import") (part "W25Q512JVEIQ"))
    )
    (comp (ref "VBAT")
      (value "TPTP20R")
      (footprint "eagle-import:TP20R")
      (libsource (lib "eagle-import") (part "TPTP20R"))
    )
    (comp (ref "VBUS")
      (value "TPTP20R")
      (footprint "eagle-import:TP20R")
      (libsource (lib "eagle-import") (part "TPTP20R"))
    )
  )
  (nets
    (net (code "1") (name "3V3") (class "Default")
      (node (ref "3V3") (pin "TP") (pinfunction "TP_TP") (pintype "input"))
      (node (ref "C1_BAT2") (pin "1") (pinfunction "1_1") (pintype "passive"))
      (node (ref "C3") (pin "+") (pinfunction "+_+") (pintype "passive"))
      (node (ref "C9") (pin "1") (pinfunction "1_1") (pintype "passive"))
      (node (ref "D7") (pin "2") (pinfunction "ANODE_2") (pintype "bidirectional"))
      (node (ref "IC1") (pin "2") (pinfunction "VDD_2") (pintype "bidirectional"))
      (node (ref "IC4") (pin "5") (pinfunction "VOUT_5") (pintype "bidirectional"))
      (node (ref "J3") (pin "2") (pinfunction "2_2") (pintype "power_in"))
      (node (ref "J4") (pin "P4") (pinfunction "VDD_P4") (pintype "bidirectional"))
      (node (ref "Q2") (pin "3") (pinfunction "D_3") (pintype "bidirectional"))
      (node (ref "R1") (pin "2") (pinfunction "2_2") (pintype "passive"))
      (node (ref "R10") (pin "2") (pinfunction "2_2") (pintype "passive"))
      (node (ref "R1_PINH1") (pin "2") (pinfunction "2_2") (pintype "passive"))
      (node (ref "R2_PINH1") (pin "2") (pinfunction "2_2") (pintype "passive"))
      (node (ref "R5") (pin "2") (pinfunction "2_2") (pintype "passive"))
      (node (ref "R6") (pin "2") (pinfunction "2_2") (pintype "passive"))
      (node (ref "R7") (pin "2") (pinfunction "2_2") (pintype "passive"))
      (node (ref "R8") (pin "2") (pinfunction "2_2") (pintype "passive"))
      (node (ref "R9") (pin "2") (pinfunction "2_2") (pintype "passive"))
      (node (ref "R_BOOT") (pin "2") (pinfunction "2_2") (pintype "passive"))
      (node (ref "R_CHANGE") (pin "2") (pinfunction "2_2") (pintype "passive"))
      (node (ref "R_CL1") (pin "2") (pinfunction "2_2") (pintype "passive"))
      (node (ref "R_RESET") (pin "2") (pinfunction "2_2") (pintype "passive"))
      (node (ref "U2") (pin "2") (pinfunction "3V3_2") (pintype "power_in"))
      (node (ref "U3") (pin "2") (pinfunction "VCC_2") (pintype "power_in"))
      (node (ref "U6") (pin "3") (pinfunction "~{WP}(IO2)_3") (pintype "bidirectional"))
      (node (ref "U6") (pin "7") (pinfunction "~{HOLD}/~{RESET}(IO3)_7") (pintype "bidirectional"))
      (node (ref "U6") (pin "8") (pinfunction "VCC_8") (pintype "power_in"))
    )
    (net (code "2") (name "32KHZ") (class "Default")
      (node (ref "R2_PINH1") (pin "1") (pinfunction "1_1") (pintype "passive"))
      (node (ref "U2") (pin "9") (pinfunction "IO1_9") (pintype "bidirectional"))
      (node (ref "U3") (pin "1") (pinfunction "32KHZ_1") (pintype "output"))
    )
    (net (code "3") (name "BOOT") (class "Default")
      (node (ref "BOOT_BUTTON") (pin "3") (pinfunction "3_3") (pintype "passive"))
      (node (ref "BOOT_BUTTON") (pin "4") (pinfunction "4_4") (pintype "passive"))
      (node (ref "C6") (pin "1") (pinfunction "1_1") (pintype "passive"))
      (node (ref "R_BOOT") (pin "1") (pinfunction "1_1") (pintype "passive"))
    )
    (net (code "4") (name "CHANGE") (class "Default")
      (node (ref "C10") (pin "1") (pinfunction "1_1") (pintype "passive"))
      (node (ref "CHANGE_BUTTON") (pin "3") (pinfunction "3_3") (pintype "passive"))
      (node (ref "CHANGE_BUTTON") (pin "4") (pinfunction "4_4") (pintype "passive"))
      (node (ref "R_CHANGE") (pin "1") (pinfunction "1_1") (pintype "passive"))
    )
    (net (code "5") (name "DN") (class "Default")
      (node (ref "D1") (pin "4") (pinfunction "I/O2_2_4") (pintype "bidirectional"))
      (node (ref "J2") (pin "A7") (pinfunction "A7_A7") (pintype "bidirectional"))
      (node (ref "J2") (pin "B7") (pinfunction "B7_B7") (pintype "bidirectional"))
    )
    (net (code "6") (name "DP") (class "Default")
      (node (ref "D1") (pin "6") (pinfunction "I/O1_2_6") (pintype "bidirectional"))
      (node (ref "J2") (pin "A6") (pinfunction "A6_A6") (pintype "bidirectional"))
      (node (ref "J2") (pin "B6") (pinfunction "B6_B6") (pintype "bidirectional"))
    )
    (net (code "7") (name "EPD_3V3") (class "Default")
      (node (ref "C7") (pin "1") (pinfunction "1_1") (pintype "passive"))
      (node (ref "EPD_3V3") (pin "TP") (pinfunction "TP_TP") (pintype "input"))
      (node (ref "EPD_C5") (pin "2") (pinfunction "2_2") (pintype "passive"))
      (node (ref "J1") (pin "15") (pinfunction "15_15") (pintype "bidirectional"))
      (node (ref "J1") (pin "16") (pinfunction "16_16") (pintype "bidirectional"))
      (node (ref "L1") (pin "2") (pinfunction "2_2") (pintype "passive"))
      (node (ref "Q2") (pin "2") (pinfunction "S_2") (pintype "bidirectional"))
    )
    (net (code "8") (name "EPD_3V3_C") (class "Default")
      (node (ref "EPD_3V3_C") (pin "TP") (pinfunction "TP_TP") (pintype "input"))
      (node (ref "Q2") (pin "1") (pinfunction "G_1") (pintype "bidirectional"))
      (node (ref "R_CL1") (pin "1") (pinfunction "1_1") (pintype "passive"))
      (node (ref "U2") (pin "18") (pinfunction "IO20_18") (pintype "bidirectional"))
    )
    (net (code "9") (name "EPD_BUSY") (class "Default")
      (node (ref "EPD_BUSY") (pin "TP") (pinfunction "TP_TP") (pintype "input"))
      (node (ref "J1") (pin "9") (pinfunction "9_9") (pintype "bidirectional"))
      (node (ref "U2") (pin "26") (pinfunction "IO3_26") (pintype "bidirectional"))
    )
    (net (code "10") (name "EPD_CS") (class "Default")
      (node (ref "D6") (pin "2") (pinfunction "2_2") (pintype "passive"))
      (node (ref "EPD_CS") (pin "TP") (pinfunction "TP_TP") (pintype "input"))
      (node (ref "J1") (pin "12") (pinfunction "12_12") (pintype "bidirectional"))
      (node (ref "R9") (pin "1") (pinfunction "1_1") (pintype "passive"))
      (node (ref "U2") (pin "11") (pinfunction "IO10_11") (pintype "bidirectional"))
    )
    (net (code "11") (name "EPD_DC") (class "Default")
      (node (ref "EPD_DC") (pin "TP") (pinfunction "TP_TP") (pintype "input"))
      (node (ref "J1") (pin "11") (pinfunction "11_11") (pintype "bidirectional"))
      (node (ref "U2") (pin "5") (pinfunction "IO5_5") (pintype "bidirectional"))
    )
    (net (code "12") (name "EPD_RST") (class "Default")
      (node (ref "EPD_RST") (pin "TP") (pinfunction "TP_TP") (pintype "input"))
      (node (ref "J1") (pin "10") (pinfunction "10_10") (pintype "bidirectional"))
      (node (ref "U2") (pin "21") (pinfunction "IO23_21") (pintype "bidirectional"))
    )
    (net (code "13") (name "FLASH_CS") (class "Default")
      (node (ref "D9") (pin "2") (pinfunction "2_2") (pintype "passive"))
      (node (ref "R5") (pin "1") (pinfunction "1_1") (pintype "passive"))
      (node (ref "U2") (pin "12") (pinfunction "IO11_12") (pintype "bidirectional"))
      (node (ref "U6") (pin "1") (pinfunction "~{CS}_1") (pintype "input"))
    )
    (net (code "14") (name "GDR") (class "Default")
      (node (ref "J1") (pin "2") (pinfunction "2_2") (pintype "bidirectional"))
      (node (ref "Q3") (pin "1") (pinfunction "G_1") (pintype "bidirectional"))
      (node (ref "R4") (pin "2") (pinfunction "2_2") (pintype "passive"))
    )
    (net (code "15") (name "GND") (class "Default")
      (node (ref "BOOT_BUTTON") (pin "1") (pinfunction "1_1") (pintype "passive"))
      (node (ref "BOOT_BUTTON") (pin "2") (pinfunction "2_2") (pintype "passive"))
      (node (ref "C1") (pin "2") (pinfunction "2_2") (pintype "passive"))
      (node (ref "C10") (pin "2") (pinfunction "2_2") (pintype "passive"))
      (node (ref "C10_SUPERCAP") (pin "1") (pinfunction "1_1") (pintype "passive"))
      (node (ref "C1_BAT") (pin "2") (pinfunction "2_2") (pintype "passive"))
      (node (ref "C1_BAT1") (pin "2") (pinfunction "2_2") (pintype "passive"))
      (node (ref "C1_BAT2") (pin "2") (pinfunction "2_2") (pintype "passive"))
      (node (ref "C2") (pin "2") (pinfunction "2_2") (pintype "passive"))
      (node (ref "C2_BAT") (pin "2") (pinfunction "2_2") (pintype "passive"))
      (node (ref "C3") (pin "-") (pinfunction "-_-") (pintype "passive"))
      (node (ref "C4_USB") (pin "2") (pinfunction "2_2") (pintype "passive"))
      (node (ref "C5") (pin "2") (pinfunction "2_2") (pintype "passive"))
      (node (ref "C5_USB") (pin "2") (pinfunction "2_2") (pintype "passive"))
      (node (ref "C6") (pin "2") (pinfunction "2_2") (pintype "passive"))
      (node (ref "C7") (pin "2") (pinfunction "2_2") (pintype "passive"))
      (node (ref "C8") (pin "2") (pinfunction "2_2") (pintype "passive"))
      (node (ref "C9") (pin "2") (pinfunction "2_2") (pintype "passive"))
      (node (ref "CHANGE_BUTTON") (pin "1") (pinfunction "1_1") (pintype "passive"))
      (node (ref "CHANGE_BUTTON") (pin "2") (pinfunction "2_2") (pintype "passive"))
      (node (ref "C_DELAY") (pin "2") (pinfunction "2_2") (pintype "passive"))
      (node (ref "D1") (pin "2") (pinfunction "GND_2") (pintype "bidirectional"))
      (node (ref "D10") (pin "1") (pinfunction "1_1") (pintype "passive"))
      (node (ref "D11") (pin "1") (pinfunction "1_1") (pintype "passive"))
      (node (ref "D12") (pin "1") (pinfunction "1_1") (pintype "passive"))
      (node (ref "D3") (pin "1") (pinfunction "K_1") (pintype "bidirectional"))
      (node (ref "D6") (pin "1") (pinfunction "1_1") (pintype "passive"))
      (node (ref "D8") (pin "1") (pinfunction "1_1") (pintype "passive"))
      (node (ref "D9") (pin "1") (pinfunction "1_1") (pintype "passive"))
      (node (ref "EPD_C1") (pin "1") (pinfunction "1_1") (pintype "passive"))
      (node (ref "EPD_C10") (pin "1") (pinfunction "1_1") (pintype "passive"))
      (node (ref "EPD_C11") (pin "1") (pinfunction "1_1") (pintype "passive"))
      (node (ref "EPD_C12") (pin "1") (pinfunction "1_1") (pintype "passive"))
      (node (ref "EPD_C2") (pin "1") (pinfunction "1_1") (pintype "passive"))
      (node (ref "EPD_C5") (pin "1") (pinfunction "1_1") (pintype "passive"))
      (node (ref "EPD_C6") (pin "1") (pinfunction "1_1") (pintype "passive"))
      (node (ref "EPD_C7") (pin "1") (pinfunction "1_1") (pintype "passive"))
      (node (ref "EPD_C8") (pin "1") (pinfunction "1_1") (pintype "passive"))
      (node (ref "EPD_C9") (pin "1") (pinfunction "1_1") (pintype "passive"))
      (node (ref "GND") (pin "TP") (pinfunction "TP_TP") (pintype "input"))
      (node (ref "GND_") (pin "TP") (pinfunction "TP_TP") (pintype "input"))
      (node (ref "IC1") (pin "3") (pinfunction "GND_3") (pintype "bidirectional"))
      (node (ref "IC4") (pin "2") (pinfunction "VSS_2") (pintype "bidirectional"))
      (node (ref "J1") (pin "17") (pinfunction "17_17") (pintype "bidirectional"))
      (node (ref "J1") (pin "8") (pinfunction "8_8") (pintype "bidirectional"))
      (node (ref "J1") (pin "MP1") (pinfunction "MP1_MP1") (pintype "bidirectional"))
      (node (ref "J1") (pin "MP2") (pinfunction "MP2_MP2") (pintype "bidirectional"))
      (node (ref "J2") (pin "A1") (pinfunction "A1_A1") (pintype "bidirectional"))
      (node (ref "J2") (pin "A12") (pinfunction "A12_A12") (pintype "bidirectional"))
      (node (ref "J2") (pin "B1") (pinfunction "B1_B1") (pintype "bidirectional"))
      (node (ref "J2") (pin "B12") (pinfunction "B12_B12") (pintype "bidirectional"))
      (node (ref "J2") (pin "MP1") (pinfunction "MP1_MP1") (pintype "bidirectional"))
      (node (ref "J2") (pin "MP2") (pinfunction "MP2_MP2") (pintype "bidirectional"))
      (node (ref "J2") (pin "MP3") (pinfunction "MP3_MP3") (pintype "bidirectional"))
      (node (ref "J2") (pin "MP4") (pinfunction "MP4_MP4") (pintype "bidirectional"))
      (node (ref "J3") (pin "1") (pinfunction "1_1") (pintype "power_in"))
      (node (ref "J4") (pin "G1") (pinfunction "GND_1_G1") (pintype "bidirectional"))
      (node (ref "J4") (pin "G2") (pinfunction "GND_2_G2") (pintype "bidirectional"))
      (node (ref "J4") (pin "G3") (pinfunction "GND_3_G3") (pintype "bidirectional"))
      (node (ref "J4") (pin "G4") (pinfunction "GND_4_G4") (pintype "bidirectional"))
      (node (ref "J4") (pin "P6") (pinfunction "VSS_P6") (pintype "bidirectional"))
      (node (ref "MCP73831") (pin "2") (pinfunction "VSS_2") (pintype "power_in"))
      (node (ref "R1_PWRUSB") (pin "1") (pinfunction "1_1") (pintype "passive"))
      (node (ref "R2") (pin "1") (pinfunction "1_1") (pintype "passive"))
      (node (ref "R2-USB") (pin "2") (pinfunction "2_2") (pintype "passive"))
      (node (ref "R2-USB1") (pin "1") (pinfunction "1_1") (pintype "passive"))
      (node (ref "R2_BAT") (pin "1") (pinfunction "1_1") (pintype "passive"))
      (node (ref "R4") (pin "1") (pinfunction "1_1") (pintype "passive"))
      (node (ref "RESET_BUTTON") (pin "1") (pinfunction "1_1") (pintype "passive"))
      (node (ref "RESET_BUTTON") (pin "2") (pinfunction "2_2") (pintype "passive"))
      (node (ref "SENSOR2") (pin "1") (pinfunction "GND_1") (pintype "power_in"))
      (node (ref "SENSOR2") (pin "5") (pinfunction "SDO_5") (pintype "bidirectional"))
      (node (ref "SENSOR2") (pin "7") (pinfunction "GND_7") (pintype "power_in"))
      (node (ref "SJ1") (pin "1") (pinfunction "1_1") (pintype "passive"))
      (node (ref "U2") (pin "1") (pinfunction "GND_1") (pintype "power_in"))
      (node (ref "U2") (pin "28") (pinfunction "GND_28") (pintype "power_in"))
      (node (ref "U2") (pin "29_1") (pinfunction "GND_29_1") (pintype "power_in"))
      (node (ref "U2") (pin "29_2") (pinfunction "GND_29_2") (pintype "power_in"))
      (node (ref "U2") (pin "29_3") (pinfunction "GND_29_3") (pintype "power_in"))
      (node (ref "U2") (pin "29_4") (pinfunction "GND_29_4") (pintype "power_in"))
      (node (ref "U2") (pin "29_5") (pinfunction "GND_29_5") (pintype "power_in"))
      (node (ref "U2") (pin "29_6") (pinfunction "GND_29_6") (pintype "power_in"))
      (node (ref "U2") (pin "29_7") (pinfunction "GND_29_7") (pintype "power_in"))
      (node (ref "U2") (pin "29_8") (pinfunction "GND_29_8") (pintype "power_in"))
      (node (ref "U2") (pin "29_9") (pinfunction "GND_29_9") (pintype "power_in"))
      (node (ref "U3") (pin "13") (pinfunction "GND_13") (pintype "power_in"))
      (node (ref "U4") (pin "1") (pinfunction "CTG_1") (pintype "power_in"))
      (node (ref "U4") (pin "4") (pinfunction "GND_4") (pintype "power_in"))
      (node (ref "U4") (pin "6") (pinfunction "QSTRT_6") (pintype "input"))
      (node (ref "U4") (pin "9") (pinfunction "EP_9") (pintype "power_in"))
      (node (ref "U6") (pin "4") (pinfunction "GND_4") (pintype "power_in"))
      (node (ref "U6") (pin "9") (pinfunction "EXP_9") (pintype "passive"))
    )
    (net (code "16") (name "GPIO8") (class "Default")
      (node (ref "R1") (pin "1") (pinfunction "1_1") (pintype "passive"))
      (node (ref "U2") (pin "10") (pinfunction "IO8_10") (pintype "bidirectional"))
    )
    (net (code "17") (name "I2C_PW") (class "Default")
      (node (ref "C1") (pin "1") (pinfunction "1_1") (pintype "passive"))
      (node (ref "C2") (pin "1") (pinfunction "1_1") (pintype "passive"))
      (node (ref "R1_PINH") (pin "2") (pinfunction "2_2") (pintype "passive"))
      (node (ref "R2_PINH") (pin "2") (pinfunction "2_2") (pintype "passive"))
      (node (ref "SENSOR2") (pin "2") (pinfunction "CSB_2") (pintype "input"))
      (node (ref "SENSOR2") (pin "6") (pinfunction "VDDIO_6") (pintype "power_in"))
      (node (ref "SENSOR2") (pin "8") (pinfunction "VDD_8") (pintype "power_in"))
      (node (ref "U2") (pin "17") (pinfunction "IO19_17") (pintype "bidirectional"))
    )
    (net (code "18") (name "INT_RTC") (class "Default")
      (node (ref "INT_RTC") (pin "TP") (pinfunction "TP_TP") (pintype "input"))
      (node (ref "R1_PINH1") (pin "1") (pinfunction "1_1") (pintype "passive"))
      (node (ref "U2") (pin "8") (pinfunction "IO0_8") (pintype "bidirectional"))
      (node (ref "U3") (pin "3") (pinfunction "SQW/~{INT}_3") (pintype "output"))
    )
    (net (code "19") (name "IO{slash}BOOT") (class "Default")
      (node (ref "U2") (pin "15") (pinfunction "IO9_15") (pintype "bidirectional"))
    )
    (net (code "20") (name "IO{slash}CHANGE") (class "Default")
      (node (ref "U2") (pin "23") (pinfunction "IO15_23") (pintype "bidirectional"))
    )
    (net (code "21") (name "MISO") (class "Default")
      (node (ref "D12") (pin "2") (pinfunction "2_2") (pintype "passive"))
      (node (ref "J4") (pin "P7") (pinfunction "DAT0_P7") (pintype "bidirectional"))
      (node (ref "MISO") (pin "TP") (pinfunction "TP_TP") (pintype "input"))
      (node (ref "R8") (pin "1") (pinfunction "1_1") (pintype "passive"))
      (node (ref "U2") (pin "27") (pinfunction "IO2_27") (pintype "bidirectional"))
      (node (ref "U6") (pin "2") (pinfunction "DO(IO1)_2") (pintype "bidirectional"))
    )
    (net (code "22") (name "MOSI") (class "Default")
      (node (ref "D11") (pin "2") (pinfunction "2_2") (pintype "passive"))
      (node (ref "J1") (pin "14") (pinfunction "14_14") (pintype "bidirectional"))
      (node (ref "J4") (pin "P3") (pinfunction "CMD_P3") (pintype "bidirectional"))
      (node (ref "MOSI") (pin "TP") (pinfunction "TP_TP") (pintype "input"))
      (node (ref "R7") (pin "1") (pinfunction "1_1") (pintype "passive"))
      (node (ref "U2") (pin "7") (pinfunction "IO7_7") (pintype "bidirectional"))
      (node (ref "U6") (pin "5") (pinfunction "DI(IO0)_5") (pintype "bidirectional"))
    )
    (net (code "23") (name "Net-(C10_SUPERCAP-Pad2)") (class "Default")
      (node (ref "C10_SUPERCAP") (pin "2") (pinfunction "2_2") (pintype "passive"))
      (node (ref "C8") (pin "1") (pinfunction "1_1") (pintype "passive"))
      (node (ref "R_CAPACITOR") (pin "2") (pinfunction "2_2") (pintype "passive"))
    )
    (net (code "24") (name "Net-(CHG_LED-PadC)") (class "Default")
      (node (ref "CHG_LED") (pin "C") (pinfunction "C_C") (pintype "passive"))
      (node (ref "R1_BAT") (pin "1") (pinfunction "1_1") (pintype "passive"))
    )
    (net (code "25") (name "Net-(D2-CATHODE)") (class "Default")
      (node (ref "C1_BAT1") (pin "1") (pinfunction "1_1") (pintype "passive"))
      (node (ref "D2") (pin "1") (pinfunction "CATHODE_1") (pintype "bidirectional"))
      (node (ref "IC4") (pin "1") (pinfunction "VIN_1") (pintype "bidirectional"))
      (node (ref "IC4") (pin "3") (pinfunction "CE_3") (pintype "bidirectional"))
      (node (ref "Q1") (pin "2") (pinfunction "S_2") (pintype "bidirectional"))
    )
    (net (code "26") (name "Net-(D3-A)") (class "Default")
      (node (ref "C4") (pin "1") (pinfunction "1_1") (pintype "passive"))
      (node (ref "D3") (pin "2") (pinfunction "A_2") (pintype "bidirectional"))
      (node (ref "D4") (pin "1") (pinfunction "K_1") (pintype "bidirectional"))
    )
    (net (code "27") (name "Net-(D7-CATHODE)") (class "Default")
      (node (ref "D7") (pin "1") (pinfunction "CATHODE_1") (pintype "bidirectional"))
      (node (ref "R_CAPACITOR") (pin "1") (pinfunction "1_1") (pintype "passive"))
    )
    (net (code "28") (name "Net-(EPD_C1-Pad2)") (class "Default")
      (node (ref "EPD_C1") (pin "2") (pinfunction "2_2") (pintype "passive"))
      (node (ref "J1") (pin "4") (pinfunction "4_4") (pintype "bidirectional"))
    )
    (net (code "29") (name "Net-(EPD_C2-Pad2)") (class "Default")
      (node (ref "EPD_C2") (pin "2") (pinfunction "2_2") (pintype "passive"))
      (node (ref "J1") (pin "5") (pinfunction "5_5") (pintype "bidirectional"))
    )
    (net (code "30") (name "Net-(EPD_C6-Pad2)") (class "Default")
      (node (ref "EPD_C6") (pin "2") (pinfunction "2_2") (pintype "passive"))
      (node (ref "J1") (pin "18") (pinfunction "18_18") (pintype "bidirectional"))
    )
    (net (code "31") (name "Net-(EPD_C7-Pad2)") (class "Default")
      (node (ref "EPD_C7") (pin "2") (pinfunction "2_2") (pintype "passive"))
      (node (ref "J1") (pin "19") (pinfunction "19_19") (pintype "bidirectional"))
    )
    (net (code "32") (name "Net-(EPD_C8-Pad2)") (class "Default")
      (node (ref "EPD_C8") (pin "2") (pinfunction "2_2") (pintype "passive"))
      (node (ref "J1") (pin "20") (pinfunction "20_20") (pintype "bidirectional"))
    )
    (net (code "33") (name "Net-(EPD_C10-Pad2)") (class "Default")
      (node (ref "EPD_C10") (pin "2") (pinfunction "2_2") (pintype "passive"))
      (node (ref "J1") (pin "22") (pinfunction "22_22") (pintype "bidirectional"))
    )
    (net (code "34") (name "Net-(EPD_C12-Pad2)") (class "Default")
      (node (ref "EPD_C12") (pin "2") (pinfunction "2_2") (pintype "passive"))
      (node (ref "J1") (pin "24") (pinfunction "24_24") (pintype "bidirectional"))
    )
    (net (code "35") (name "Net-(IC1-CT)") (class "Default")
      (node (ref "C_DELAY") (pin "1") (pinfunction "1_1") (pintype "passive"))
      (node (ref "IC1") (pin "5") (pinfunction "CT_5") (pintype "bidirectional"))
    )
    (net (code "36") (name "Net-(J2-PadA5)") (class "Default")
      (node (ref "J2") (pin "A5") (pinfunction "A5_A5") (pintype "bidirectional"))
      (node (ref "R2-USB1") (pin "2") (pinfunction "2_2") (pintype "passive"))
    )
    (net (code "37") (name "Net-(J2-PadB5)") (class "Default")
      (node (ref "J2") (pin "B5") (pinfunction "B5_B5") (pintype "bidirectional"))
      (node (ref "R2-USB") (pin "1") (pinfunction "1_1") (pintype "passive"))
    )
    (net (code "38") (name "Net-(MCP73831-PROG)") (class "Default")
      (node (ref "MCP73831") (pin "5") (pinfunction "PROG_5") (pintype "input"))
      (node (ref "R2_BAT") (pin "2") (pinfunction "2_2") (pintype "passive"))
    )
    (net (code "39") (name "Net-(MCP73831-STAT)") (class "Default")
      (node (ref "MCP73831") (pin "1") (pinfunction "STAT_1") (pintype "output"))
      (node (ref "R1_BAT") (pin "2") (pinfunction "2_2") (pintype "passive"))
    )
    (net (code "40") (name "PREVGH") (class "Default")
      (node (ref "D5") (pin "1") (pinfunction "K_1") (pintype "bidirectional"))
      (node (ref "EPD_C9") (pin "2") (pinfunction "2_2") (pintype "passive"))
      (node (ref "J1") (pin "21") (pinfunction "21_21") (pintype "bidirectional"))
    )
    (net (code "41") (name "PREVGL") (class "Default")
      (node (ref "D4") (pin "2") (pinfunction "A_2") (pintype "bidirectional"))
      (node (ref "EPD_C11") (pin "2") (pinfunction "2_2") (pintype "passive"))
      (node (ref "J1") (pin "23") (pinfunction "23_23") (pintype "bidirectional"))
    )
    (net (code "42") (name "RESE") (class "Default")
      (node (ref "J1") (pin "3") (pinfunction "3_3") (pintype "bidirectional"))
      (node (ref "Q3") (pin "2") (pinfunction "S_2") (pintype "bidirectional"))
      (node (ref "R3") (pin "2") (pinfunction "2_2") (pintype "passive"))
    )
    (net (code "43") (name "RESE'") (class "Default")
      (node (ref "R2") (pin "2") (pinfunction "2_2") (pintype "passive"))
      (node (ref "R3") (pin "1") (pinfunction "1_1") (pintype "passive"))
      (node (ref "SJ1") (pin "2") (pinfunction "2_2") (pintype "passive"))
    )
    (net (code "44") (name "RESET") (class "Default")
      (node (ref "C5") (pin "1") (pinfunction "1_1") (pintype "passive"))
      (node (ref "IC1") (pin "1") (pinfunction "VOUT_1") (pintype "bidirectional"))
      (node (ref "RESET_BUTTON") (pin "3") (pinfunction "3_3") (pintype "passive"))
      (node (ref "RESET_BUTTON") (pin "4") (pinfunction "4_4") (pintype "passive"))
      (node (ref "R_RESET") (pin "1") (pinfunction "1_1") (pintype "passive"))
      (node (ref "U2") (pin "3") (pinfunction "EN_3") (pintype "input"))
    )
    (net (code "45") (name "RTC_RST") (class "Default")
      (node (ref "U2") (pin "16") (pinfunction "IO18_16") (pintype "bidirectional"))
      (node (ref "U3") (pin "4") (pinfunction "~{RST}_4") (pintype "input"))
    )
    (net (code "46") (name "RX") (class "Default")
      (node (ref "RX") (pin "TP") (pinfunction "TP_TP") (pintype "input"))
      (node (ref "U2") (pin "24") (pinfunction "RXD0/GPIO17_24") (pintype "bidirectional"))
    )
    (net (code "47") (name "SCK") (class "Default")
      (node (ref "D10") (pin "2") (pinfunction "2_2") (pintype "passive"))
      (node (ref "J1") (pin "13") (pinfunction "13_13") (pintype "bidirectional"))
      (node (ref "J4") (pin "P5") (pinfunction "CLK_P5") (pintype "bidirectional"))
      (node (ref "R6") (pin "1") (pinfunction "1_1") (pintype "passive"))
      (node (ref "SCK") (pin "TP") (pinfunction "TP_TP") (pintype "input"))
      (node (ref "U2") (pin "6") (pinfunction "IO6_6") (pintype "bidirectional"))
      (node (ref "U6") (pin "6") (pinfunction "CLK_6") (pintype "input"))
    )
    (net (code "48") (name "SCL") (class "Default")
      (node (ref "J3") (pin "4") (pinfunction "4_4") (pintype "passive"))
      (node (ref "R2_PINH") (pin "1") (pinfunction "1_1") (pintype "passive"))
      (node (ref "SENSOR2") (pin "4") (pinfunction "SCK_4") (pintype "input"))
      (node (ref "U2") (pin "20") (pinfunction "IO22_20") (pintype "bidirectional"))
      (node (ref "U3") (pin "16") (pinfunction "SCL_16") (pintype "input"))
      (node (ref "U4") (pin "7") (pinfunction "SCL_7") (pintype "input"))
    )
    (net (code "49") (name "SDA") (class "Default")
      (node (ref "J3") (pin "3") (pinfunction "3_3") (pintype "passive"))
      (node (ref "R1_PINH") (pin "1") (pinfunction "1_1") (pintype "passive"))
      (node (ref "SENSOR2") (pin "3") (pinfunction "SDI_3") (pintype "bidirectional"))
      (node (ref "U2") (pin "19") (pinfunction "IO21_19") (pintype "bidirectional"))
      (node (ref "U3") (pin "15") (pinfunction "SDA_15") (pintype "bidirectional"))
      (node (ref "U4") (pin "8") (pinfunction "SDA_8") (pintype "bidirectional"))
    )
    (net (code "50") (name "SRC") (class "Default")
      (node (ref "C4") (pin "2") (pinfunction "2_2") (pintype "passive"))
      (node (ref "D5") (pin "2") (pinfunction "A_2") (pintype "bidirectional"))
      (node (ref "L1") (pin "1") (pinfunction "1_1") (pintype "passive"))
      (node (ref "Q3") (pin "3") (pinfunction "D_3") (pintype "bidirectional"))
    )
    (net (code "51") (name "SS_SD") (class "Default")
      (node (ref "D8") (pin "2") (pinfunction "2_2") (pintype "passive"))
      (node (ref "J4") (pin "P2") (pinfunction "CD/DAT3_P2") (pintype "bidirectional"))
      (node (ref "R10") (pin "1") (pinfunction "1_1") (pintype "passive"))
      (node (ref "U2") (pin "4") (pinfunction "IO4_4") (pintype "bidirectional"))
    )
    (net (code "52") (name "TX") (class "Default")
      (node (ref "TX") (pin "TP") (pinfunction "TP_TP") (pintype "input"))
      (node (ref "U2") (pin "25") (pinfunction "TXD0/GPIO16_25") (pintype "bidirectional"))
    )
    (net (code "53") (name "USB_D+") (class "Default")
      (node (ref "D1") (pin "1") (pinfunction "I/O1_1_1") (pintype "bidirectional"))
      (node (ref "U2") (pin "14") (pinfunction "IO13_14") (pintype "bidirectional"))
    )
    (net (code "54") (name "USB_D-") (class "Default")
      (node (ref "D1") (pin "3") (pinfunction "I/O2_1_3") (pintype "bidirectional"))
      (node (ref "U2") (pin "13") (pinfunction "IO12_13") (pintype "bidirectional"))
    )
    (net (code "55") (name "VBAT") (class "Default")
      (node (ref "C2_BAT") (pin "1") (pinfunction "1_1") (pintype "passive"))
      (node (ref "MCP73831") (pin "3") (pinfunction "VBAT_3") (pintype "power_in"))
      (node (ref "Q1") (pin "3") (pinfunction "D_3") (pintype "bidirectional"))
      (node (ref "U4") (pin "2") (pinfunction "CELL_2") (pintype "power_in"))
      (node (ref "U4") (pin "3") (pinfunction "VDD_3") (pintype "power_in"))
      (node (ref "VBAT") (pin "TP") (pinfunction "TP_TP") (pintype "input"))
    )
    (net (code "56") (name "VBUS") (class "Default")
      (node (ref "C1_BAT") (pin "1") (pinfunction "1_1") (pintype "passive"))
      (node (ref "C4_USB") (pin "1") (pinfunction "1_1") (pintype "passive"))
      (node (ref "C5_USB") (pin "1") (pinfunction "1_1") (pintype "passive"))
      (node (ref "CHG_LED") (pin "A") (pinfunction "A_A") (pintype "passive"))
      (node (ref "D1") (pin "5") (pinfunction "VBUS_5") (pintype "bidirectional"))
      (node (ref "D2") (pin "2") (pinfunction "ANODE_2") (pintype "bidirectional"))
      (node (ref "MCP73831") (pin "4") (pinfunction "VIN_4") (pintype "power_in"))
      (node (ref "PFMF.050.1") (pin "2") (pinfunction "2_2") (pintype "passive"))
      (node (ref "Q1") (pin "1") (pinfunction "G_1") (pintype "bidirectional"))
      (node (ref "R1_PWRUSB") (pin "2") (pinfunction "2_2") (pintype "passive"))
      (node (ref "VBUS") (pin "TP") (pinfunction "TP_TP") (pintype "input"))
    )
    (net (code "57") (name "VRTC") (class "Default")
      (node (ref "U3") (pin "14") (pinfunction "VBAT_14") (pintype "power_in"))
    )
    (net (code "58") (name "VUSB") (class "Default")
      (node (ref "J2") (pin "A4") (pinfunction "A4_A4") (pintype "bidirectional"))
      (node (ref "J2") (pin "A9") (pinfunction "A9_A9") (pintype "bidirectional"))
      (node (ref "J2") (pin "B4") (pinfunction "B4_B4") (pintype "bidirectional"))
      (node (ref "J2") (pin "B9") (pinfunction "B9_B9") (pintype "bidirectional"))
      (node (ref "PFMF.050.1") (pin "1") (pinfunction "1_1") (pintype "passive"))
    )
    (net (code "59") (name "unconnected-(IC1-NC-Pad4)") (class "Default")
      (node (ref "IC1") (pin "4") (pinfunction "NC_4") (pintype "no_connect"))
    )
    (net (code "60") (name "unconnected-(IC4-NC-Pad4)") (class "Default")
      (node (ref "IC4") (pin "4") (pinfunction "NC_4") (pintype "no_connect"))
    )
    (net (code "61") (name "unconnected-(J1-Pad1)") (class "Default")
      (node (ref "J1") (pin "1") (pinfunction "1_1") (pintype "bidirectional"))
    )
    (net (code "62") (name "unconnected-(J1-Pad6)") (class "Default")
      (node (ref "J1") (pin "6") (pinfunction "6_6") (pintype "bidirectional"))
    )
    (net (code "63") (name "unconnected-(J1-Pad7)") (class "Default")
      (node (ref "J1") (pin "7") (pinfunction "7_7") (pintype "bidirectional"))
    )
    (net (code "64") (name "unconnected-(J2-PadA8)") (class "Default")
      (node (ref "J2") (pin "A8") (pinfunction "A8_A8") (pintype "bidirectional"))
    )
    (net (code "65") (name "unconnected-(J2-PadB8)") (class "Default")
      (node (ref "J2") (pin "B8") (pinfunction "B8_B8") (pintype "bidirectional"))
    )
    (net (code "66") (name "unconnected-(J4-DAT1-PadP8)") (class "Default")
      (node (ref "J4") (pin "P8") (pinfunction "DAT1_P8") (pintype "bidirectional"))
    )
    (net (code "67") (name "unconnected-(J4-DAT2-PadP1)") (class "Default")
      (node (ref "J4") (pin "P1") (pinfunction "DAT2_P1") (pintype "bidirectional"))
    )
    (net (code "68") (name "unconnected-(J4-DETECTION_1-PadS1)") (class "Default")
      (node (ref "J4") (pin "S1") (pinfunction "DETECTION_1_S1") (pintype "bidirectional"))
    )
    (net (code "69") (name "unconnected-(J4-DETECTION_2-PadS2)") (class "Default")
      (node (ref "J4") (pin "S2") (pinfunction "DETECTION_2_S2") (pintype "bidirectional"))
    )
    (net (code "70") (name "unconnected-(U2-NC-Pad22)") (class "Default")
      (node (ref "U2") (pin "22") (pinfunction "NC_22") (pintype "no_connect"))
    )
    (net (code "71") (name "unconnected-(U4-~{ALERT}-Pad5)") (class "Default")
      (node (ref "U4") (pin "5") (pinfunction "~{ALERT}_5") (pintype "output"))
    )
  )
)
